# RPi-WD-Packet-Interface_-_9pinDSub.net
KiCad netlist of a schematic drawn in EAGLE
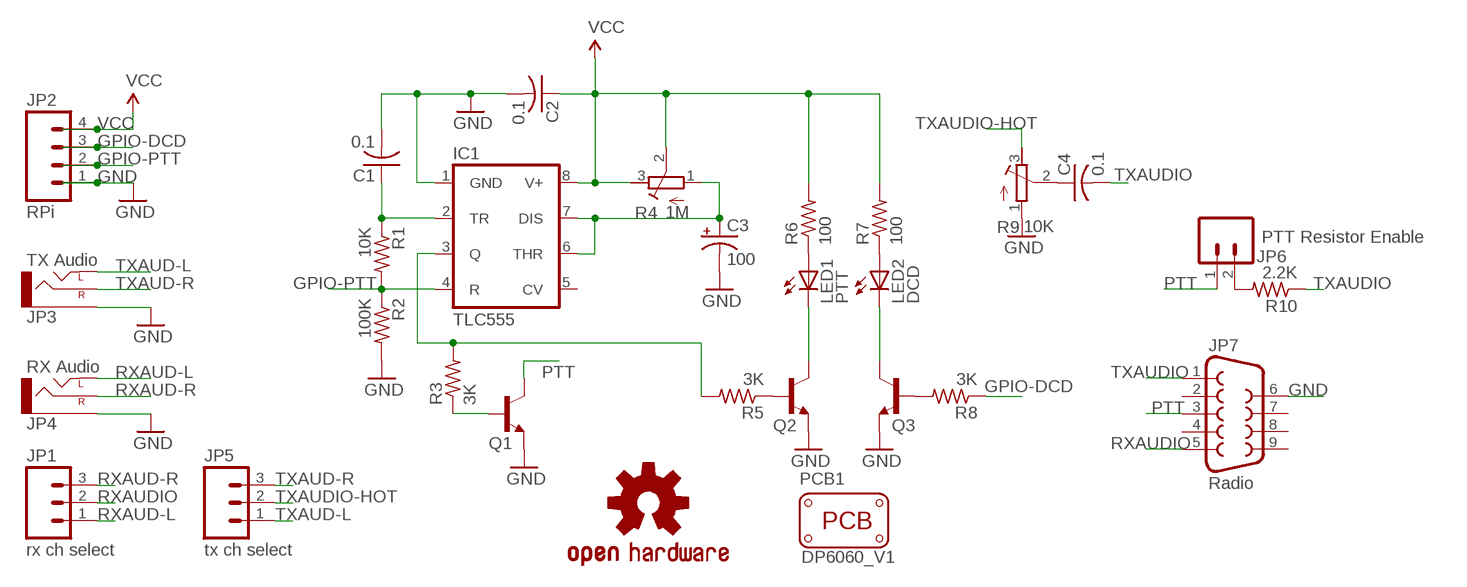
[diagram p0: schematic, sheet 1]

(export (version "E")
  (design (tool "Eeschema 10.0.6"))
  (components
    (comp (ref "C1")
      (value "0.1")
      (footprint "eagle-import:C025-025X050")
      (libsource (lib "eagle-import") (part "C-US025-025X050"))
    )
    (comp (ref "C2")
      (value "0.1")
      (footprint "eagle-import:C025-025X050")
      (libsource (lib "eagle-import") (part "C-US025-025X050"))
    )
    (comp (ref "C3")
      (value "100")
      (footprint "eagle-import:E2-5")
      (libsource (lib "eagle-import") (part "CPOL-USE2-5"))
    )
    (comp (ref "C4")
      (value "0.1")
      (footprint "eagle-import:C025-025X050")
      (libsource (lib "eagle-import") (part "C-US025-025X050"))
    )
    (comp (ref "IC1")
      (value "TLC555")
      (footprint "eagle-import:DIL08")
      (libsource (lib "eagle-import") (part "555NLM"))
    )
    (comp (ref "JP1")
      (value "rx ch select")
      (footprint "eagle-import:1X03")
      (libsource (lib "eagle-import") (part "M03PTH"))
    )
    (comp (ref "JP2")
      (value "RPi")
      (footprint "eagle-import:1X04")
      (libsource (lib "eagle-import") (part "M04PTH"))
    )
    (comp (ref "JP3")
      (value "TX Audio")
      (footprint "eagle-import:AUDIO-JACK")
      (libsource (lib "eagle-import") (part "AUDIO-JACKPTH"))
    )
    (comp (ref "JP4")
      (value "RX Audio")
      (footprint "eagle-import:AUDIO-JACK")
      (libsource (lib "eagle-import") (part "AUDIO-JACKPTH"))
    )
    (comp (ref "JP5")
      (value "tx ch select")
      (footprint "eagle-import:1X03")
      (libsource (lib "eagle-import") (part "M03PTH"))
    )
    (comp (ref "JP6")
      (value "PTT Resistor Enable")
      (footprint "eagle-import:1X02")
      (libsource (lib "eagle-import") (part "M02PTH"))
    )
    (comp (ref "JP7")
      (value "Radio")
      (footprint "eagle-import:DB9")
      (libsource (lib "eagle-import") (part "DB9FEMALE"))
    )
    (comp (ref "LED1")
      (value "PTT")
      (footprint "eagle-import:LED5MM")
      (libsource (lib "eagle-import") (part "LED5MM"))
    )
    (comp (ref "LED2")
      (value "DCD")
      (footprint "eagle-import:LED5MM")
      (libsource (lib "eagle-import") (part "LED5MM"))
    )
    (comp (ref "LOGO1")
      (value "OSHW-LOGOM")
      (footprint "eagle-import:OSHW-LOGO-M")
      (libsource (lib "eagle-import") (part "OSHW-LOGOM"))
    )
    (comp (ref "PCB1")
      (value "PCB_DP_SQUARE-6X6")
      (footprint "eagle-import:DP6060_V1")
      (libsource (lib "eagle-import") (part "PCB_DP_SQUARE-6X6"))
    )
    (comp (ref "Q1")
      (value "PTT")
      (footprint "eagle-import:TO-92-AMMO")
      (libsource (lib "eagle-import") (part "TRANSISTOR_NPNTO-92-AMMO"))
    )
    (comp (ref "Q2")
      (value "PTT-LED")
      (footprint "eagle-import:TO-92-AMMO")
      (libsource (lib "eagle-import") (part "TRANSISTOR_NPNTO-92-AMMO"))
    )
    (comp (ref "Q3")
      (value "DCD-LED")
      (footprint "eagle-import:TO-92-AMMO")
      (libsource (lib "eagle-import") (part "TRANSISTOR_NPNTO-92-AMMO"))
    )
    (comp (ref "R1")
      (value "10K")
      (footprint "eagle-import:0207_7")
      (libsource (lib "eagle-import") (part "R-US_0207/7"))
    )
    (comp (ref "R2")
      (value "100K")
      (footprint "eagle-import:0207_7")
      (libsource (lib "eagle-import") (part "R-US_0207/7"))
    )
    (comp (ref "R3")
      (value "3K")
      (footprint "eagle-import:0207_7")
      (libsource (lib "eagle-import") (part "R-US_0207/7"))
    )
    (comp (ref "R4")
      (value "1M")
      (footprint "eagle-import:RTRIM3296W")
      (libsource (lib "eagle-import") (part "R-TRIMM3296W"))
    )
    (comp (ref "R5")
      (value "3K")
      (footprint "eagle-import:0207_7")
      (libsource (lib "eagle-import") (part "R-US_0207/7"))
    )
    (comp (ref "R6")
      (value "100")
      (footprint "eagle-import:0207_7")
      (libsource (lib "eagle-import") (part "R-US_0207/7"))
    )
    (comp (ref "R7")
      (value "100")
      (footprint "eagle-import:0207_7")
      (libsource (lib "eagle-import") (part "R-US_0207/7"))
    )
    (comp (ref "R8")
      (value "3K")
      (footprint "eagle-import:0207_7")
      (libsource (lib "eagle-import") (part "R-US_0207/7"))
    )
    (comp (ref "R9")
      (value "10K")
      (footprint "eagle-import:RTRIM3362P")
      (libsource (lib "eagle-import") (part "RTRIM-3362P"))
    )
    (comp (ref "R10")
      (value "2.2K")
      (footprint "eagle-import:0207_7")
      (libsource (lib "eagle-import") (part "R-US_0207/7"))
    )
  )
  (nets
    (net (code "1") (name "/GPIO-DCD") (class "Default")
      (node (ref "JP2") (pin "3") (pinfunction "3_3") (pintype "passive"))
      (node (ref "R8") (pin "1") (pinfunction "1_1") (pintype "passive"))
    )
    (net (code "2") (name "/GPIO-PTT") (class "Default")
      (node (ref "IC1") (pin "4") (pinfunction "R_4") (pintype "input"))
      (node (ref "JP2") (pin "2") (pinfunction "2_2") (pintype "passive"))
      (node (ref "R1") (pin "2") (pinfunction "2_2") (pintype "passive"))
      (node (ref "R2") (pin "1") (pinfunction "1_1") (pintype "passive"))
    )
    (net (code "3") (name "/PTT") (class "Default")
      (node (ref "JP6") (pin "1") (pinfunction "1_1") (pintype "passive"))
      (node (ref "JP7") (pin "3") (pinfunction "3_3") (pintype "passive"))
      (node (ref "Q1") (pin "3") (pinfunction "C_3") (pintype "passive"))
    )
    (net (code "4") (name "/RXAUD-L") (class "Default")
      (node (ref "JP1") (pin "1") (pinfunction "1_1") (pintype "passive"))
      (node (ref "JP4") (pin "TIP") (pinfunction "LEFT_TIP") (pintype "bidirectional"))
    )
    (net (code "5") (name "/RXAUD-R") (class "Default")
      (node (ref "JP1") (pin "3") (pinfunction "3_3") (pintype "passive"))
      (node (ref "JP4") (pin "RING") (pinfunction "RIGHT_RING") (pintype "bidirectional"))
    )
    (net (code "6") (name "/RXAUDIO") (class "Default")
      (node (ref "JP1") (pin "2") (pinfunction "2_2") (pintype "passive"))
      (node (ref "JP7") (pin "5") (pinfunction "5_5") (pintype "passive"))
    )
    (net (code "7") (name "/TXAUD-L") (class "Default")
      (node (ref "JP3") (pin "TIP") (pinfunction "LEFT_TIP") (pintype "bidirectional"))
      (node (ref "JP5") (pin "1") (pinfunction "1_1") (pintype "passive"))
    )
    (net (code "8") (name "/TXAUD-R") (class "Default")
      (node (ref "JP3") (pin "RING") (pinfunction "RIGHT_RING") (pintype "bidirectional"))
      (node (ref "JP5") (pin "3") (pinfunction "3_3") (pintype "passive"))
    )
    (net (code "9") (name "/TXAUDIO") (class "Default")
      (node (ref "C4") (pin "2") (pinfunction "2_2") (pintype "passive"))
      (node (ref "JP7") (pin "1") (pinfunction "1_1") (pintype "passive"))
      (node (ref "R10") (pin "1") (pinfunction "1_1") (pintype "passive"))
    )
    (net (code "10") (name "/TXAUDIO-HOT") (class "Default")
      (node (ref "JP5") (pin "2") (pinfunction "2_2") (pintype "passive"))
      (node (ref "R9") (pin "3") (pinfunction "3_3") (pintype "passive"))
    )
    (net (code "11") (name "GND") (class "Default")
      (node (ref "C1") (pin "2") (pinfunction "2_2") (pintype "passive"))
      (node (ref "C2") (pin "2") (pinfunction "2_2") (pintype "passive"))
      (node (ref "C3") (pin "-") (pinfunction "-_-") (pintype "passive"))
      (node (ref "IC1") (pin "1") (pinfunction "GND_1") (pintype "power_in"))
      (node (ref "JP2") (pin "1") (pinfunction "1_1") (pintype "passive"))
      (node (ref "JP3") (pin "SLEEVE") (pinfunction "SLEEVE_SLEEVE") (pintype "bidirectional"))
      (node (ref "JP4") (pin "SLEEVE") (pinfunction "SLEEVE_SLEEVE") (pintype "bidirectional"))
      (node (ref "JP7") (pin "6") (pinfunction "6_6") (pintype "passive"))
      (node (ref "Q1") (pin "1") (pinfunction "E_1") (pintype "passive"))
      (node (ref "Q2") (pin "1") (pinfunction "E_1") (pintype "passive"))
      (node (ref "Q3") (pin "1") (pinfunction "E_1") (pintype "passive"))
      (node (ref "R2") (pin "2") (pinfunction "2_2") (pintype "passive"))
      (node (ref "R9") (pin "1") (pinfunction "1_1") (pintype "passive"))
    )
    (net (code "12") (name "Net-(C4-Pad1)") (class "Default")
      (node (ref "C4") (pin "1") (pinfunction "1_1") (pintype "passive"))
      (node (ref "R9") (pin "2") (pinfunction "2_2") (pintype "passive"))
    )
    (net (code "13") (name "Net-(IC1-DIS)") (class "Default")
      (node (ref "C3") (pin "+") (pinfunction "+_+") (pintype "passive"))
      (node (ref "IC1") (pin "6") (pinfunction "THR_6") (pintype "input"))
      (node (ref "IC1") (pin "7") (pinfunction "DIS_7") (pintype "input"))
      (node (ref "R4") (pin "1") (pinfunction "A_1") (pintype "passive"))
    )
    (net (code "14") (name "Net-(IC1-Q)") (class "Default")
      (node (ref "IC1") (pin "3") (pinfunction "Q_3") (pintype "output"))
      (node (ref "R3") (pin "2") (pinfunction "2_2") (pintype "passive"))
      (node (ref "R5") (pin "2") (pinfunction "2_2") (pintype "passive"))
    )
    (net (code "15") (name "Net-(IC1-TR)") (class "Default")
      (node (ref "C1") (pin "1") (pinfunction "1_1") (pintype "passive"))
      (node (ref "IC1") (pin "2") (pinfunction "TR_2") (pintype "input"))
      (node (ref "R1") (pin "1") (pinfunction "1_1") (pintype "passive"))
    )
    (net (code "16") (name "Net-(JP6-Pad2)") (class "Default")
      (node (ref "JP6") (pin "2") (pinfunction "2_2") (pintype "passive"))
      (node (ref "R10") (pin "2") (pinfunction "2_2") (pintype "passive"))
    )
    (net (code "17") (name "Net-(LED1-C)") (class "Default")
      (node (ref "LED1") (pin "K") (pinfunction "C_K") (pintype "passive"))
      (node (ref "Q2") (pin "3") (pinfunction "C_3") (pintype "passive"))
    )
    (net (code "18") (name "Net-(LED1-PadA)") (class "Default")
      (node (ref "LED1") (pin "A") (pinfunction "A_A") (pintype "passive"))
      (node (ref "R6") (pin "1") (pinfunction "1_1") (pintype "passive"))
    )
    (net (code "19") (name "Net-(LED2-C)") (class "Default")
      (node (ref "LED2") (pin "K") (pinfunction "C_K") (pintype "passive"))
      (node (ref "Q3") (pin "3") (pinfunction "C_3") (pintype "passive"))
    )
    (net (code "20") (name "Net-(LED2-PadA)") (class "Default")
      (node (ref "LED2") (pin "A") (pinfunction "A_A") (pintype "passive"))
      (node (ref "R7") (pin "1") (pinfunction "1_1") (pintype "passive"))
    )
    (net (code "21") (name "Net-(Q1-B)") (class "Default")
      (node (ref "Q1") (pin "2") (pinfunction "B_2") (pintype "passive"))
      (node (ref "R3") (pin "1") (pinfunction "1_1") (pintype "passive"))
    )
    (net (code "22") (name "Net-(Q2-B)") (class "Default")
      (node (ref "Q2") (pin "2") (pinfunction "B_2") (pintype "passive"))
      (node (ref "R5") (pin "1") (pinfunction "1_1") (pintype "passive"))
    )
    (net (code "23") (name "Net-(Q3-B)") (class "Default")
      (node (ref "Q3") (pin "2") (pinfunction "B_2") (pintype "passive"))
      (node (ref "R8") (pin "2") (pinfunction "2_2") (pintype "passive"))
    )
    (net (code "24") (name "VCC") (class "Default")
      (node (ref "C2") (pin "1") (pinfunction "1_1") (pintype "passive"))
      (node (ref "IC1") (pin "8") (pinfunction "V+_8") (pintype "power_in"))
      (node (ref "JP2") (pin "4") (pinfunction "4_4") (pintype "passive"))
      (node (ref "R4") (pin "2") (pinfunction "S_2") (pintype "passive"))
      (node (ref "R4") (pin "3") (pinfunction "E_3") (pintype "passive"))
      (node (ref "R6") (pin "2") (pinfunction "2_2") (pintype "passive"))
      (node (ref "R7") (pin "2") (pinfunction "2_2") (pintype "passive"))
    )
    (net (code "25") (name "unconnected-(IC1-CV-Pad5)") (class "Default")
      (node (ref "IC1") (pin "5") (pinfunction "CV_5") (pintype "input"))
    )
    (net (code "26") (name "unconnected-(JP7-Pad2)") (class "Default")
      (node (ref "JP7") (pin "2") (pinfunction "2_2") (pintype "passive"))
    )
    (net (code "27") (name "unconnected-(JP7-Pad4)") (class "Default")
      (node (ref "JP7") (pin "4") (pinfunction "4_4") (pintype "passive"))
    )
    (net (code "28") (name "unconnected-(JP7-Pad7)") (class "Default")
      (node (ref "JP7") (pin "7") (pinfunction "7_7") (pintype "passive"))
    )
    (net (code "29") (name "unconnected-(JP7-Pad8)") (class "Default")
      (node (ref "JP7") (pin "8") (pinfunction "8_8") (pintype "passive"))
    )
    (net (code "30") (name "unconnected-(JP7-Pad9)") (class "Default")
      (node (ref "JP7") (pin "9") (pinfunction "9_9") (pintype "passive"))
    )
  )
)
